# StmPulse-V1-G498043.net
KiCad netlist of a schematic drawn in EAGLE
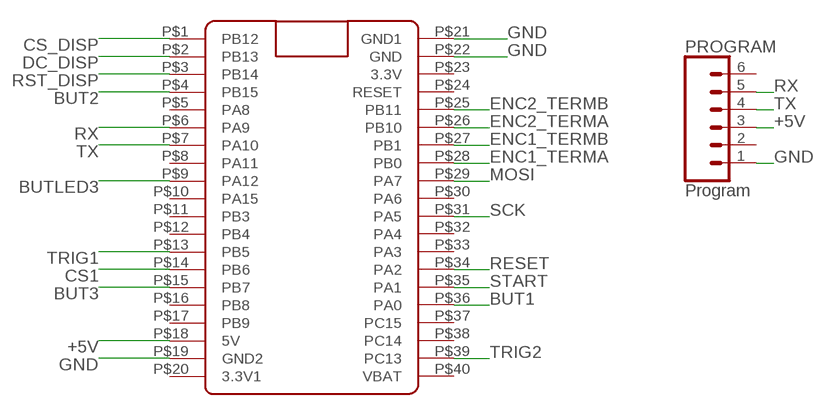
[diagram p0: schematic, sheet 1]
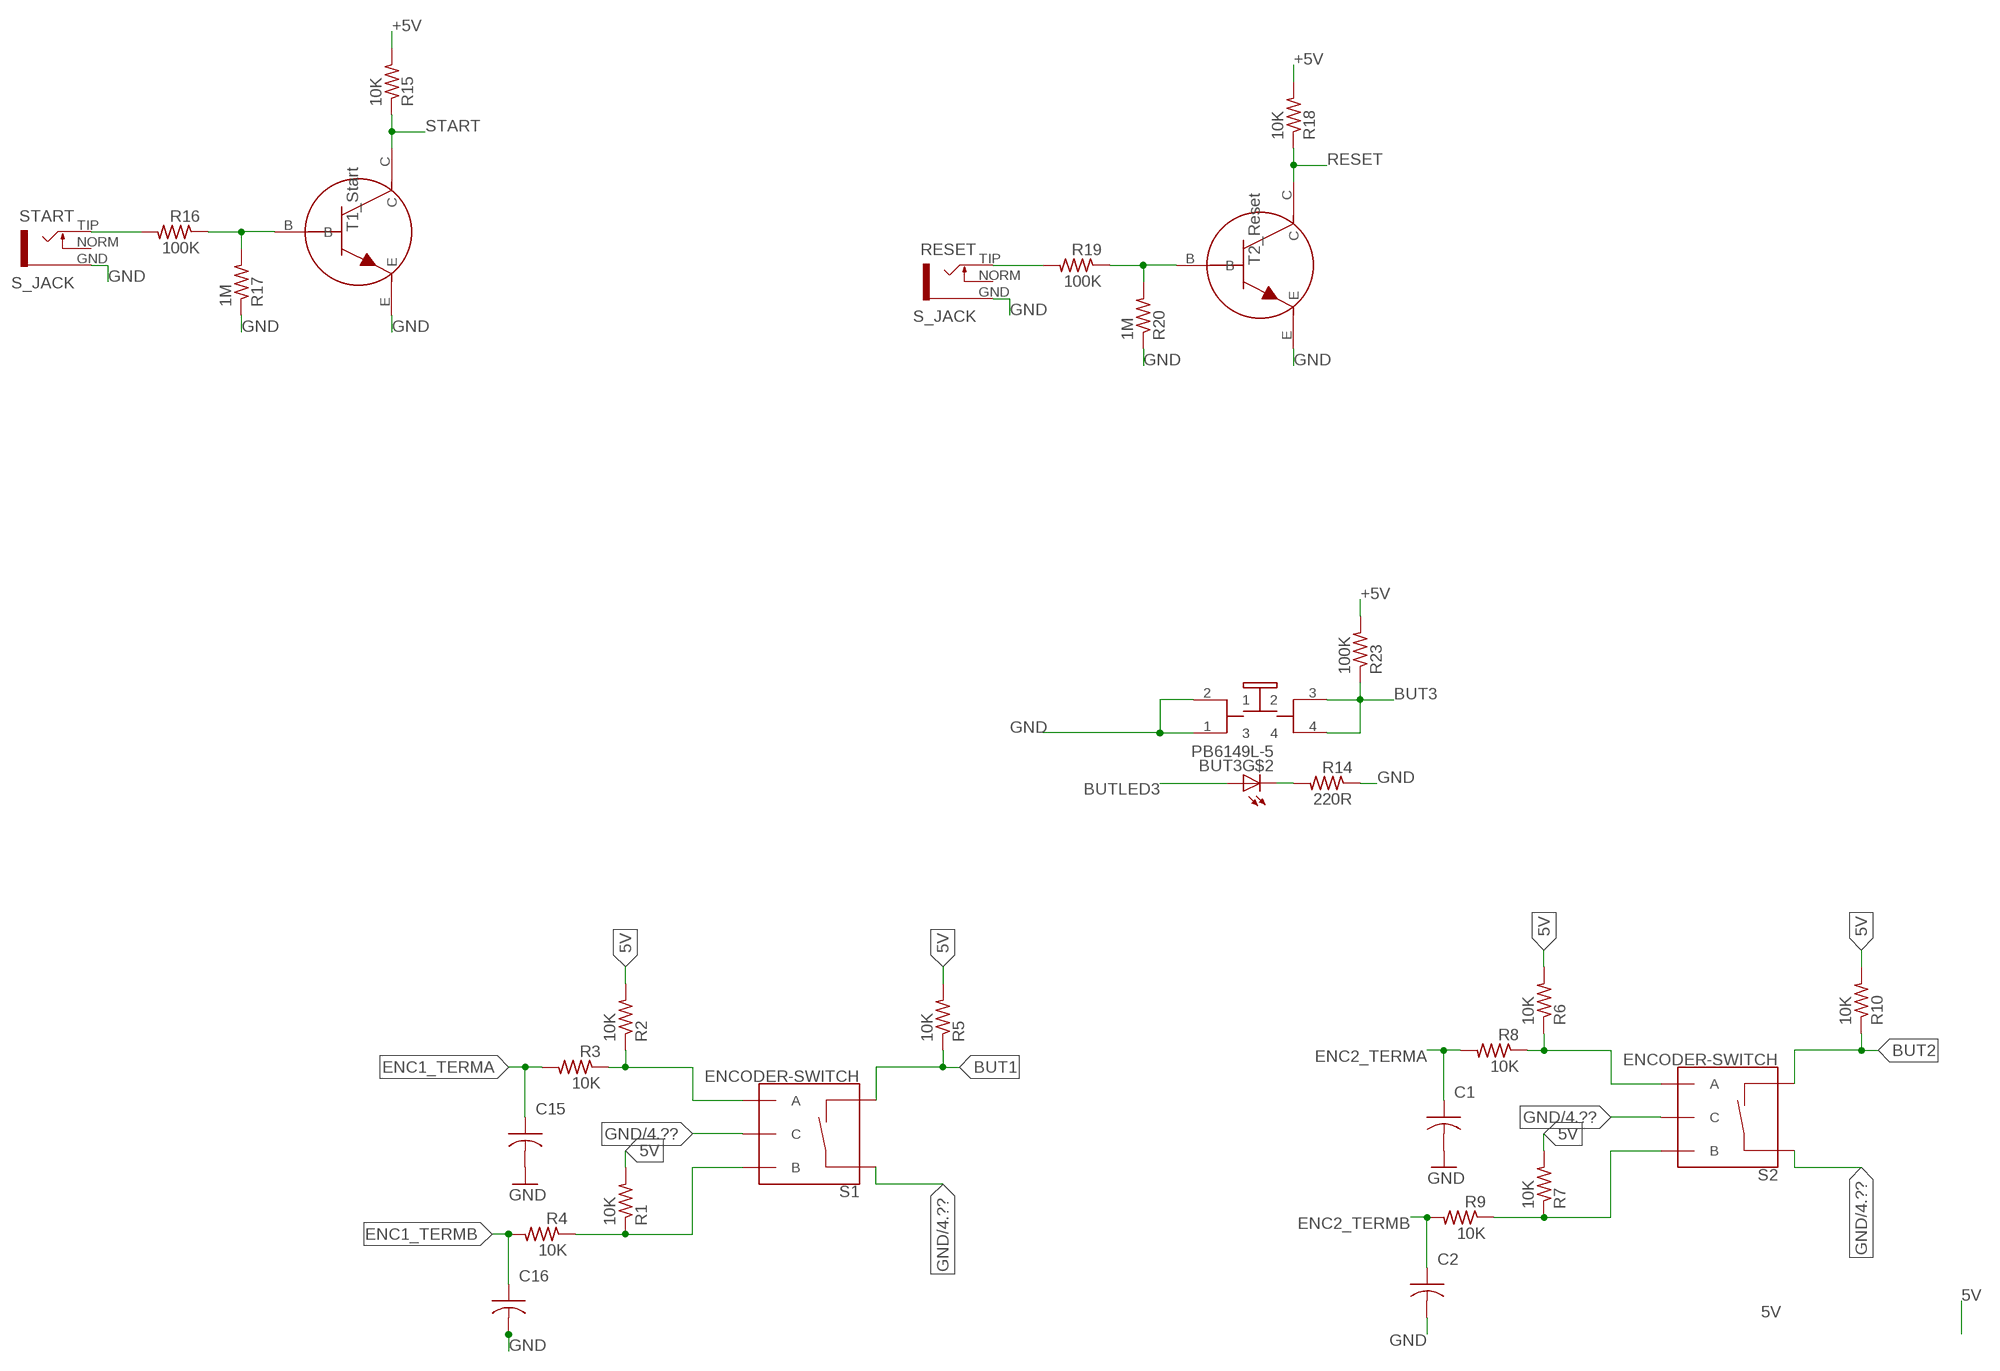
[diagram p1: schematic, sheet 2]
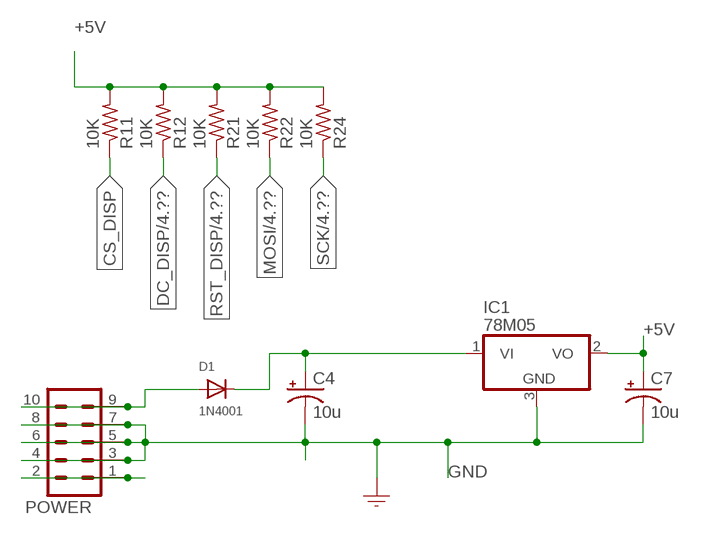
[diagram p2: schematic, sheet 3]
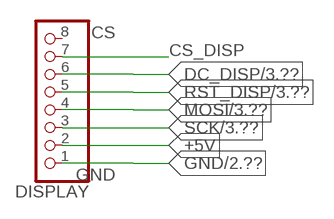
[diagram p3: schematic, sheet 4]
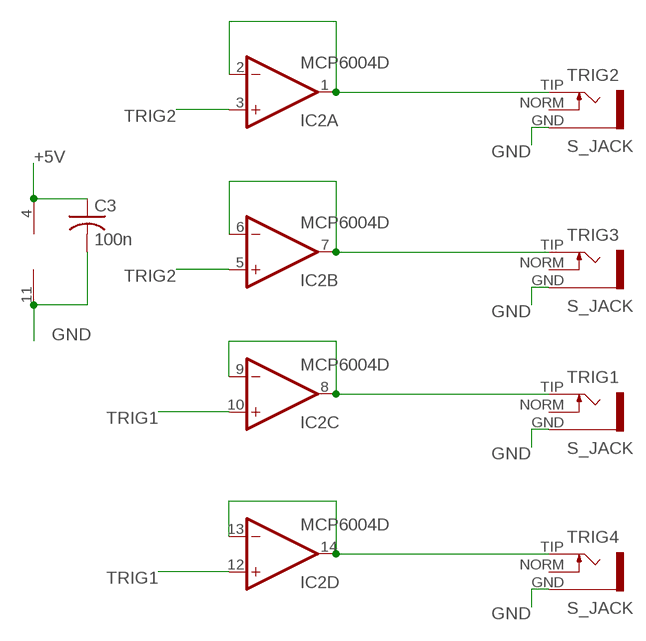
[diagram p4: schematic, sheet 5]
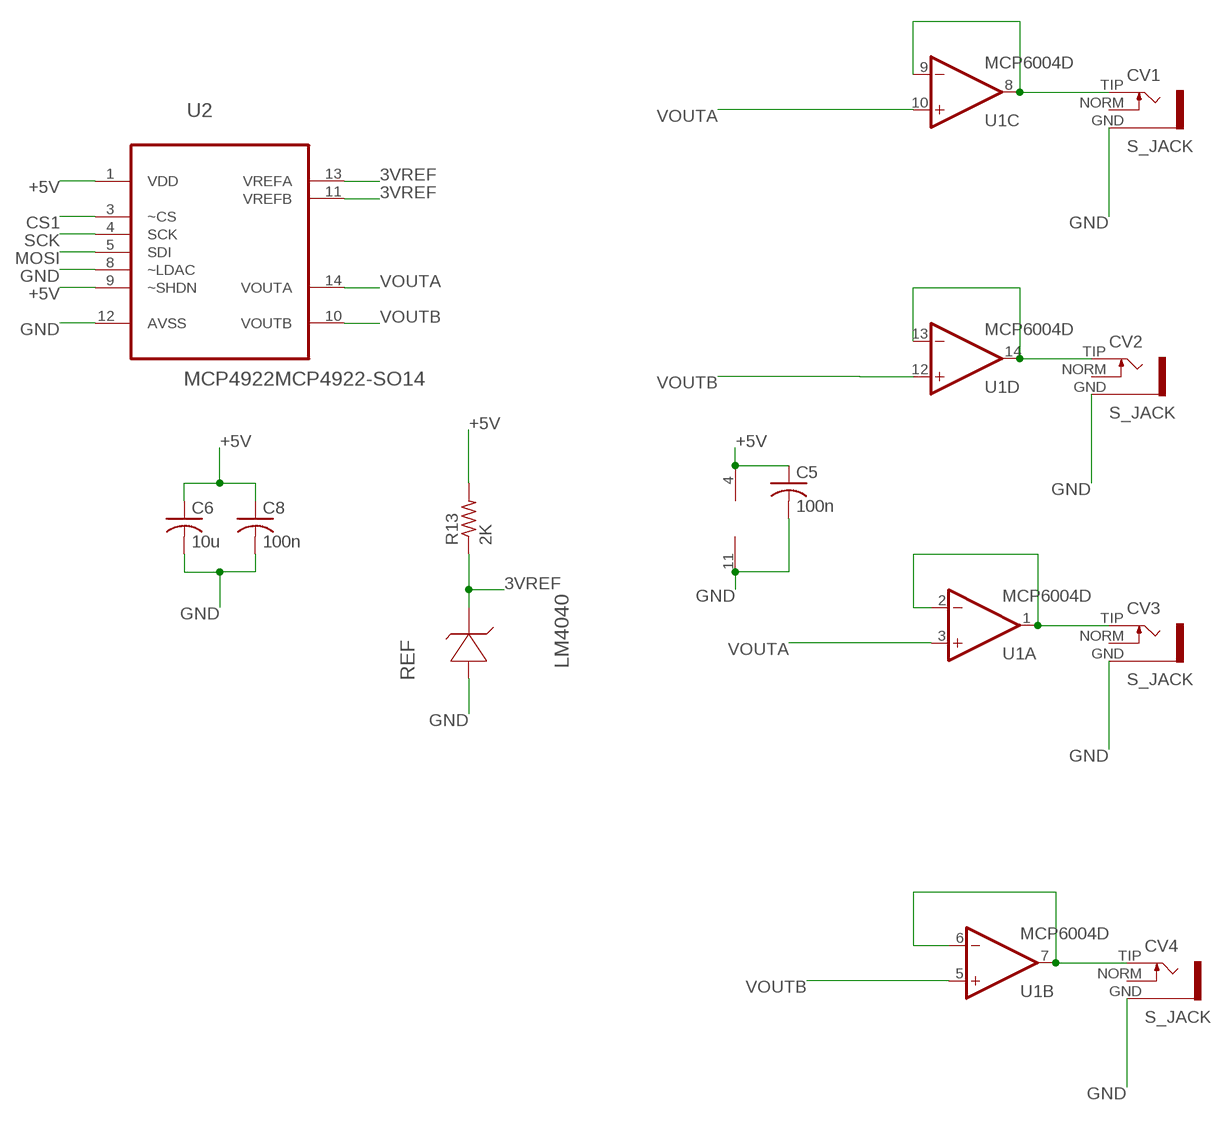
[diagram p5: schematic, sheet 6]

(export (version "E")
  (design (tool "Eeschema 10.0.6"))
  (components
    (comp (ref "C5")
      (value "100n")
      (footprint "eagle-import:C0805K")
      (libsource (lib "eagle-import") (part "C-USC0805K"))
    )
    (comp (ref "C6")
      (value "10u")
      (footprint "eagle-import:C0805K")
      (libsource (lib "eagle-import") (part "C-USC0805K"))
    )
    (comp (ref "C8")
      (value "100n")
      (footprint "eagle-import:C0805K")
      (libsource (lib "eagle-import") (part "C-USC0805K"))
    )
    (comp (ref "CV1")
      (value "S_JACK")
      (footprint "eagle-import:S_JACK")
      (libsource (lib "eagle-import") (part "S_JACK"))
    )
    (comp (ref "CV2")
      (value "S_JACK")
      (footprint "eagle-import:S_JACK")
      (libsource (lib "eagle-import") (part "S_JACK"))
    )
    (comp (ref "CV3")
      (value "S_JACK")
      (footprint "eagle-import:S_JACK")
      (libsource (lib "eagle-import") (part "S_JACK"))
    )
    (comp (ref "CV4")
      (value "S_JACK")
      (footprint "eagle-import:S_JACK")
      (libsource (lib "eagle-import") (part "S_JACK"))
    )
    (comp (ref "R13")
      (value "2K")
      (footprint "eagle-import:R0805")
      (libsource (lib "eagle-import") (part "R-US_R0805"))
    )
    (comp (ref "REF")
      (value "LM4040")
      (footprint "eagle-import:SOT95P237X112-3N")
      (fields
        (field (name "MPN") "LM4040A50IDBZT")
        (field (name "MPN_1") "LM4040A30IDBZT")
        (field (name "RS-PART") "809-6343")
      )
      (libsource (lib "eagle-import") (part "LM4040A30IDBZT"))
    )
    (comp (ref "U1")
      (value "MCP6004D")
      (footprint "eagle-import:SO14")
      (fields (field (name "RS-PART") "628-3481 (10)"))
      (libsource (lib "eagle-import") (part "MCP6004D"))
    )
    (comp (ref "U2")
      (value "MCP4922MCP4922-SO14")
      (footprint "eagle-import:SO14")
      (fields (field (name "RS-PART") "402-910 "))
      (libsource (lib "eagle-import") (part "MCP4922MCP4922-SO14"))
    )
    (comp (ref "C3")
      (value "100n")
      (footprint "eagle-import:C0805K")
      (libsource (lib "eagle-import") (part "C-USC0805K"))
    )
    (comp (ref "IC2")
      (value "MCP6004D")
      (footprint "eagle-import:SO14")
      (libsource (lib "eagle-import") (part "MCP6004D"))
    )
    (comp (ref "TRIG1")
      (value "S_JACK")
      (footprint "eagle-import:S_JACK")
      (libsource (lib "eagle-import") (part "S_JACK"))
    )
    (comp (ref "TRIG2")
      (value "S_JACK")
      (footprint "eagle-import:S_JACK")
      (libsource (lib "eagle-import") (part "S_JACK"))
    )
    (comp (ref "TRIG3")
      (value "S_JACK")
      (footprint "eagle-import:S_JACK")
      (libsource (lib "eagle-import") (part "S_JACK"))
    )
    (comp (ref "TRIG4")
      (value "S_JACK")
      (footprint "eagle-import:S_JACK")
      (libsource (lib "eagle-import") (part "S_JACK"))
    )
    (comp (ref "PROGRAM")
      (value "Program")
      (footprint "eagle-import:1X06")
      (libsource (lib "eagle-import") (part "CONN_06SILK_FEMALE_PTH"))
    )
    (comp (ref "U$1")
      (value "Blue Pill")
      (footprint "eagle-import:BLUE_PILL")
      (libsource (lib "eagle-import") (part "BLUE_PILL"))
    )
    (comp (ref "DISPLAY")
      (value "MICROBUILDER_HEADER-1X8ROUND")
      (footprint "eagle-import:MICROBUILDER_1X08_ROUND")
      (libsource (lib "eagle-import") (part "MICROBUILDER_HEADER-1X8ROUND"))
    )
    (comp (ref "C4")
      (value "10u")
      (footprint "eagle-import:153CLV-0505")
      (libsource (lib "eagle-import") (part "CAPACITOR_POL-US153CLV-0505"))
    )
    (comp (ref "C7")
      (value "10u")
      (footprint "eagle-import:153CLV-0505")
      (libsource (lib "eagle-import") (part "CAPACITOR_POL-US153CLV-0505"))
    )
    (comp (ref "D1")
      (value "1N4001")
      (footprint "eagle-import:SMADIODE")
      (libsource (lib "eagle-import") (part "DIODESMA"))
    )
    (comp (ref "IC1")
      (value "78M05")
      (footprint "eagle-import:TO252")
      (libsource (lib "eagle-import") (part "VOLTAGE_REG_POSDT05"))
    )
    (comp (ref "POWER")
      (value "CONN_05X2SHD_SMD")
      (footprint "eagle-import:2X5-SHROUDED_SMD")
      (fields (field (name "RS-PART") "828-1783"))
      (libsource (lib "eagle-import") (part "CONN_05X2SHD_SMD"))
    )
    (comp (ref "R11")
      (value "10K")
      (footprint "eagle-import:R0805")
      (libsource (lib "eagle-import") (part "R-US_R0805"))
    )
    (comp (ref "R12")
      (value "10K")
      (footprint "eagle-import:R0805")
      (libsource (lib "eagle-import") (part "R-US_R0805"))
    )
    (comp (ref "R21")
      (value "10K")
      (footprint "eagle-import:R0805")
      (libsource (lib "eagle-import") (part "R-US_R0805"))
    )
    (comp (ref "R22")
      (value "10K")
      (footprint "eagle-import:R0805")
      (libsource (lib "eagle-import") (part "R-US_R0805"))
    )
    (comp (ref "R24")
      (value "10K")
      (footprint "eagle-import:R0805")
      (libsource (lib "eagle-import") (part "R-US_R0805"))
    )
    (comp (ref "BUT3")
      (value "PB6149L-5")
      (footprint "eagle-import:PB6149L")
      (libsource (lib "eagle-import") (part "PB6149L-5"))
    )
    (comp (ref "C1")
      (value "10nF")
      (footprint "eagle-import:C0805")
      (libsource (lib "eagle-import") (part "C-USC0805"))
    )
    (comp (ref "C2")
      (value "10nF")
      (footprint "eagle-import:C0805")
      (libsource (lib "eagle-import") (part "C-USC0805"))
    )
    (comp (ref "C15")
      (value "10nF")
      (footprint "eagle-import:C0805")
      (libsource (lib "eagle-import") (part "C-USC0805"))
    )
    (comp (ref "C16")
      (value "10nF")
      (footprint "eagle-import:C0805")
      (libsource (lib "eagle-import") (part "C-USC0805"))
    )
    (comp (ref "R1")
      (value "10K")
      (footprint "eagle-import:R0805")
      (libsource (lib "eagle-import") (part "R-US_R0805"))
    )
    (comp (ref "R2")
      (value "10K")
      (footprint "eagle-import:R0805")
      (libsource (lib "eagle-import") (part "R-US_R0805"))
    )
    (comp (ref "R3")
      (value "10K")
      (footprint "eagle-import:R0805")
      (libsource (lib "eagle-import") (part "R-US_R0805"))
    )
    (comp (ref "R4")
      (value "10K")
      (footprint "eagle-import:R0805")
      (libsource (lib "eagle-import") (part "R-US_R0805"))
    )
    (comp (ref "R5")
      (value "10K")
      (footprint "eagle-import:R0805")
      (libsource (lib "eagle-import") (part "R-US_R0805"))
    )
    (comp (ref "R6")
      (value "10K")
      (footprint "eagle-import:R0805")
      (libsource (lib "eagle-import") (part "R-US_R0805"))
    )
    (comp (ref "R7")
      (value "10K")
      (footprint "eagle-import:R0805")
      (libsource (lib "eagle-import") (part "R-US_R0805"))
    )
    (comp (ref "R8")
      (value "10K")
      (footprint "eagle-import:R0805")
      (libsource (lib "eagle-import") (part "R-US_R0805"))
    )
    (comp (ref "R9")
      (value "10K")
      (footprint "eagle-import:R0805")
      (libsource (lib "eagle-import") (part "R-US_R0805"))
    )
    (comp (ref "R10")
      (value "10K")
      (footprint "eagle-import:R0805")
      (libsource (lib "eagle-import") (part "R-US_R0805"))
    )
    (comp (ref "R14")
      (value "220R")
      (footprint "eagle-import:R0805")
      (libsource (lib "eagle-import") (part "R-US_R0805"))
    )
    (comp (ref "R15")
      (value "10K")
      (footprint "eagle-import:R0805")
      (libsource (lib "eagle-import") (part "R-US_R0805"))
    )
    (comp (ref "R16")
      (value "100K")
      (footprint "eagle-import:R0805")
      (libsource (lib "eagle-import") (part "R-US_R0805"))
    )
    (comp (ref "R17")
      (value "1M")
      (footprint "eagle-import:R0805")
      (libsource (lib "eagle-import") (part "R-US_R0805"))
    )
    (comp (ref "R18")
      (value "10K")
      (footprint "eagle-import:R0805")
      (libsource (lib "eagle-import") (part "R-US_R0805"))
    )
    (comp (ref "R19")
      (value "100K")
      (footprint "eagle-import:R0805")
      (libsource (lib "eagle-import") (part "R-US_R0805"))
    )
    (comp (ref "R20")
      (value "1M")
      (footprint "eagle-import:R0805")
      (libsource (lib "eagle-import") (part "R-US_R0805"))
    )
    (comp (ref "R23")
      (value "100K")
      (footprint "eagle-import:R0805")
      (libsource (lib "eagle-import") (part "R-US_R0805"))
    )
    (comp (ref "RESET")
      (value "S_JACK")
      (footprint "eagle-import:S_JACK")
      (libsource (lib "eagle-import") (part "S_JACK"))
    )
    (comp (ref "S1")
      (value "ENCODER-SWITCH")
      (footprint "eagle-import:ROTARY_ENC_PLAIN")
      (libsource (lib "eagle-import") (part "ENCODER-SWITCH"))
    )
    (comp (ref "S2")
      (value "ENCODER-SWITCH")
      (footprint "eagle-import:ROTARY_ENC_PLAIN")
      (libsource (lib "eagle-import") (part "ENCODER-SWITCH"))
    )
    (comp (ref "START")
      (value "S_JACK")
      (footprint "eagle-import:S_JACK")
      (libsource (lib "eagle-import") (part "S_JACK"))
    )
    (comp (ref "T1_CLOCK")
      (value "2N3904")
      (footprint "eagle-import:TRANSISTOR_SINGLE_N-TYPE")
      (fields (field (name "LABLEL") "T1_Start") (field (name "RS-PART") "725-8616 "))
      (libsource (lib "eagle-import") (part "TRANSISTOR_MMBT3904"))
    )
    (comp (ref "T2_RESET")
      (value "TRANSISTOR_MMBT3904")
      (footprint "eagle-import:TRANSISTOR_SINGLE_N-TYPE")
      (fields (field (name "LABEL") "T2_Reset") (field (name "RS-PART") "725-8616 "))
      (libsource (lib "eagle-import") (part "TRANSISTOR_MMBT3904"))
    )
  )
  (nets
    (net (code "1") (name "+5V") (class "Default")
      (node (ref "C3") (pin "1") (pinfunction "1_1") (pintype "passive"))
      (node (ref "C5") (pin "1") (pinfunction "1_1") (pintype "passive"))
      (node (ref "C6") (pin "1") (pinfunction "1_1") (pintype "passive"))
      (node (ref "C7") (pin "+") (pinfunction "+_+") (pintype "passive"))
      (node (ref "C8") (pin "1") (pinfunction "1_1") (pintype "passive"))
      (node (ref "DISPLAY") (pin "2") (pinfunction "2_2") (pintype "passive"))
      (node (ref "IC1") (pin "2") (pinfunction "VO_2") (pintype "passive"))
      (node (ref "IC2") (pin "4") (pinfunction "V+_4") (pintype "power_in"))
      (node (ref "PROGRAM") (pin "3") (pinfunction "3_3") (pintype "passive"))
      (node (ref "R11") (pin "2") (pinfunction "2_2") (pintype "passive"))
      (node (ref "R12") (pin "2") (pinfunction "2_2") (pintype "passive"))
      (node (ref "R13") (pin "2") (pinfunction "2_2") (pintype "passive"))
      (node (ref "R15") (pin "2") (pinfunction "2_2") (pintype "passive"))
      (node (ref "R18") (pin "2") (pinfunction "2_2") (pintype "passive"))
      (node (ref "R21") (pin "2") (pinfunction "2_2") (pintype "passive"))
      (node (ref "R22") (pin "2") (pinfunction "2_2") (pintype "passive"))
      (node (ref "R23") (pin "2") (pinfunction "2_2") (pintype "passive"))
      (node (ref "R24") (pin "2") (pinfunction "2_2") (pintype "passive"))
      (node (ref "U$1") (pin "P$18") (pinfunction "5V_P$18") (pintype "bidirectional"))
      (node (ref "U1") (pin "4") (pinfunction "V+_4") (pintype "power_in"))
      (node (ref "U2") (pin "1") (pinfunction "VDD_1") (pintype "power_in"))
      (node (ref "U2") (pin "9") (pinfunction "~{SHDN}_9") (pintype "bidirectional"))
    )
    (net (code "2") (name "3VREF") (class "Default")
      (node (ref "R13") (pin "1") (pinfunction "1_1") (pintype "passive"))
      (node (ref "REF") (pin "1") (pinfunction "CATHODE_1") (pintype "output"))
      (node (ref "U2") (pin "11") (pinfunction "VREFB_11") (pintype "bidirectional"))
      (node (ref "U2") (pin "13") (pinfunction "VREFA_13") (pintype "input"))
    )
    (net (code "3") (name "5V") (class "Default")
      (node (ref "R1") (pin "2") (pinfunction "2_2") (pintype "passive"))
      (node (ref "R10") (pin "2") (pinfunction "2_2") (pintype "passive"))
      (node (ref "R2") (pin "2") (pinfunction "2_2") (pintype "passive"))
      (node (ref "R5") (pin "2") (pinfunction "2_2") (pintype "passive"))
      (node (ref "R6") (pin "2") (pinfunction "2_2") (pintype "passive"))
      (node (ref "R7") (pin "2") (pinfunction "2_2") (pintype "passive"))
    )
    (net (code "4") (name "BUT1") (class "Default")
      (node (ref "R5") (pin "1") (pinfunction "1_1") (pintype "passive"))
      (node (ref "S1") (pin "SW-") (pinfunction "SW-_SW-") (pintype "bidirectional"))
      (node (ref "U$1") (pin "P$36") (pinfunction "PA0_P$36") (pintype "bidirectional"))
    )
    (net (code "5") (name "BUT2") (class "Default")
      (node (ref "R10") (pin "1") (pinfunction "1_1") (pintype "passive"))
      (node (ref "S2") (pin "SW-") (pinfunction "SW-_SW-") (pintype "bidirectional"))
      (node (ref "U$1") (pin "P$4") (pinfunction "PB15_P$4") (pintype "bidirectional"))
    )
    (net (code "6") (name "BUT3") (class "Default")
      (node (ref "BUT3") (pin "3") (pinfunction "2_3") (pintype "bidirectional"))
      (node (ref "BUT3") (pin "4") (pinfunction "4_4") (pintype "bidirectional"))
      (node (ref "R23") (pin "1") (pinfunction "1_1") (pintype "passive"))
      (node (ref "U$1") (pin "P$15") (pinfunction "PB7_P$15") (pintype "bidirectional"))
    )
    (net (code "7") (name "BUTLED3") (class "Default")
      (node (ref "BUT3") (pin "A") (pinfunction "A_A") (pintype "passive"))
      (node (ref "U$1") (pin "P$9") (pinfunction "PA12_P$9") (pintype "bidirectional"))
    )
    (net (code "8") (name "CS1") (class "Default")
      (node (ref "U$1") (pin "P$14") (pinfunction "PB6_P$14") (pintype "bidirectional"))
      (node (ref "U2") (pin "3") (pinfunction "~{CS}_3") (pintype "input"))
    )
    (net (code "9") (name "CS_DISP") (class "Default")
      (node (ref "DISPLAY") (pin "7") (pinfunction "7_7") (pintype "passive"))
      (node (ref "R11") (pin "1") (pinfunction "1_1") (pintype "passive"))
      (node (ref "U$1") (pin "P$1") (pinfunction "PB12_P$1") (pintype "bidirectional"))
    )
    (net (code "10") (name "DC_DISP") (class "Default")
      (node (ref "DISPLAY") (pin "6") (pinfunction "6_6") (pintype "passive"))
      (node (ref "R12") (pin "1") (pinfunction "1_1") (pintype "passive"))
      (node (ref "U$1") (pin "P$2") (pinfunction "PB13_P$2") (pintype "bidirectional"))
    )
    (net (code "11") (name "ENC1_TERMA") (class "Default")
      (node (ref "C15") (pin "1") (pinfunction "1_1") (pintype "passive"))
      (node (ref "R3") (pin "2") (pinfunction "2_2") (pintype "passive"))
      (node (ref "U$1") (pin "P$28") (pinfunction "PB0_P$28") (pintype "bidirectional"))
    )
    (net (code "12") (name "ENC1_TERMB") (class "Default")
      (node (ref "C16") (pin "1") (pinfunction "1_1") (pintype "passive"))
      (node (ref "R4") (pin "2") (pinfunction "2_2") (pintype "passive"))
      (node (ref "U$1") (pin "P$27") (pinfunction "PB1_P$27") (pintype "bidirectional"))
    )
    (net (code "13") (name "ENC2_TERMA") (class "Default")
      (node (ref "C1") (pin "1") (pinfunction "1_1") (pintype "passive"))
      (node (ref "R8") (pin "2") (pinfunction "2_2") (pintype "passive"))
      (node (ref "U$1") (pin "P$26") (pinfunction "PB10_P$26") (pintype "bidirectional"))
    )
    (net (code "14") (name "ENC2_TERMB") (class "Default")
      (node (ref "C2") (pin "1") (pinfunction "1_1") (pintype "passive"))
      (node (ref "R9") (pin "2") (pinfunction "2_2") (pintype "passive"))
      (node (ref "U$1") (pin "P$25") (pinfunction "PB11_P$25") (pintype "bidirectional"))
    )
    (net (code "15") (name "GND") (class "Default")
      (node (ref "BUT3") (pin "1") (pinfunction "3_1") (pintype "bidirectional"))
      (node (ref "BUT3") (pin "2") (pinfunction "1_2") (pintype "bidirectional"))
      (node (ref "C1") (pin "2") (pinfunction "2_2") (pintype "passive"))
      (node (ref "C15") (pin "2") (pinfunction "2_2") (pintype "passive"))
      (node (ref "C16") (pin "2") (pinfunction "2_2") (pintype "passive"))
      (node (ref "C2") (pin "2") (pinfunction "2_2") (pintype "passive"))
      (node (ref "C3") (pin "2") (pinfunction "2_2") (pintype "passive"))
      (node (ref "C4") (pin "-") (pinfunction "-_-") (pintype "passive"))
      (node (ref "C5") (pin "2") (pinfunction "2_2") (pintype "passive"))
      (node (ref "C6") (pin "2") (pinfunction "2_2") (pintype "passive"))
      (node (ref "C7") (pin "-") (pinfunction "-_-") (pintype "passive"))
      (node (ref "C8") (pin "2") (pinfunction "2_2") (pintype "passive"))
      (node (ref "CV1") (pin "GND") (pinfunction "GND_GND") (pintype "passive"))
      (node (ref "CV2") (pin "GND") (pinfunction "GND_GND") (pintype "passive"))
      (node (ref "CV3") (pin "GND") (pinfunction "GND_GND") (pintype "passive"))
      (node (ref "CV4") (pin "GND") (pinfunction "GND_GND") (pintype "passive"))
      (node (ref "DISPLAY") (pin "1") (pinfunction "1_1") (pintype "passive"))
      (node (ref "IC1") (pin "3") (pinfunction "GND_3") (pintype "passive"))
      (node (ref "IC2") (pin "11") (pinfunction "V-_11") (pintype "power_in"))
      (node (ref "POWER") (pin "3") (pinfunction "3_3") (pintype "passive"))
      (node (ref "POWER") (pin "4") (pinfunction "4_4") (pintype "passive"))
      (node (ref "POWER") (pin "5") (pinfunction "5_5") (pintype "passive"))
      (node (ref "POWER") (pin "6") (pinfunction "6_6") (pintype "passive"))
      (node (ref "POWER") (pin "7") (pinfunction "7_7") (pintype "passive"))
      (node (ref "POWER") (pin "8") (pinfunction "8_8") (pintype "passive"))
      (node (ref "PROGRAM") (pin "1") (pinfunction "1_1") (pintype "passive"))
      (node (ref "R14") (pin "1") (pinfunction "1_1") (pintype "passive"))
      (node (ref "R17") (pin "1") (pinfunction "1_1") (pintype "passive"))
      (node (ref "R20") (pin "1") (pinfunction "1_1") (pintype "passive"))
      (node (ref "REF") (pin "2") (pinfunction "ANODE_2") (pintype "input"))
      (node (ref "RESET") (pin "GND") (pinfunction "GND_GND") (pintype "passive"))
      (node (ref "S1") (pin "C") (pinfunction "C_C") (pintype "bidirectional"))
      (node (ref "S1") (pin "SW+") (pinfunction "SW+_SW+") (pintype "bidirectional"))
      (node (ref "S2") (pin "C") (pinfunction "C_C") (pintype "bidirectional"))
      (node (ref "S2") (pin "SW+") (pinfunction "SW+_SW+") (pintype "bidirectional"))
      (node (ref "START") (pin "GND") (pinfunction "GND_GND") (pintype "passive"))
      (node (ref "T1_CLOCK") (pin "E") (pinfunction "E_E") (pintype "bidirectional"))
      (node (ref "T2_RESET") (pin "E") (pinfunction "E_E") (pintype "bidirectional"))
      (node (ref "TRIG1") (pin "GND") (pinfunction "GND_GND") (pintype "passive"))
      (node (ref "TRIG2") (pin "GND") (pinfunction "GND_GND") (pintype "passive"))
      (node (ref "TRIG3") (pin "GND") (pinfunction "GND_GND") (pintype "passive"))
      (node (ref "TRIG4") (pin "GND") (pinfunction "GND_GND") (pintype "passive"))
      (node (ref "U$1") (pin "P$19") (pinfunction "GND2_P$19") (pintype "bidirectional"))
      (node (ref "U$1") (pin "P$21") (pinfunction "GND1_P$21") (pintype "power_in"))
      (node (ref "U$1") (pin "P$22") (pinfunction "GND_P$22") (pintype "bidirectional"))
      (node (ref "U1") (pin "11") (pinfunction "V-_11") (pintype "power_in"))
      (node (ref "U2") (pin "12") (pinfunction "AVSS_12") (pintype "passive"))
      (node (ref "U2") (pin "8") (pinfunction "~{LDAC}_8") (pintype "input"))
    )
    (net (code "16") (name "MOSI") (class "Default")
      (node (ref "DISPLAY") (pin "4") (pinfunction "4_4") (pintype "passive"))
      (node (ref "R22") (pin "1") (pinfunction "1_1") (pintype "passive"))
      (node (ref "U$1") (pin "P$29") (pinfunction "PA7_P$29") (pintype "bidirectional"))
      (node (ref "U2") (pin "5") (pinfunction "SDI_5") (pintype "input"))
    )
    (net (code "17") (name "Net-(BUT3B-C)") (class "Default")
      (node (ref "BUT3") (pin "K") (pinfunction "C_K") (pintype "passive"))
      (node (ref "R14") (pin "2") (pinfunction "2_2") (pintype "passive"))
    )
    (net (code "18") (name "Net-(D1-PadA)") (class "Default")
      (node (ref "D1") (pin "A") (pinfunction "A_A") (pintype "passive"))
      (node (ref "POWER") (pin "10") (pinfunction "10_10") (pintype "passive"))
      (node (ref "POWER") (pin "9") (pinfunction "9_9") (pintype "passive"))
    )
    (net (code "19") (name "Net-(IC1-VI)") (class "Default")
      (node (ref "C4") (pin "+") (pinfunction "+_+") (pintype "passive"))
      (node (ref "D1") (pin "C") (pinfunction "C_C") (pintype "passive"))
      (node (ref "IC1") (pin "1") (pinfunction "VI_1") (pintype "input"))
    )
    (net (code "20") (name "Net-(IC2A--IN)") (class "Default")
      (node (ref "IC2") (pin "1") (pinfunction "OUT_1") (pintype "output"))
      (node (ref "IC2") (pin "2") (pinfunction "-IN_2") (pintype "input"))
      (node (ref "TRIG2") (pin "TIP") (pinfunction "TIP_TIP") (pintype "passive"))
    )
    (net (code "21") (name "Net-(IC2B--IN)") (class "Default")
      (node (ref "IC2") (pin "6") (pinfunction "-IN_6") (pintype "input"))
      (node (ref "IC2") (pin "7") (pinfunction "OUT_7") (pintype "output"))
      (node (ref "TRIG3") (pin "TIP") (pinfunction "TIP_TIP") (pintype "passive"))
    )
    (net (code "22") (name "Net-(IC2C--IN)") (class "Default")
      (node (ref "IC2") (pin "8") (pinfunction "OUT_8") (pintype "output"))
      (node (ref "IC2") (pin "9") (pinfunction "-IN_9") (pintype "input"))
      (node (ref "TRIG1") (pin "TIP") (pinfunction "TIP_TIP") (pintype "passive"))
    )
    (net (code "23") (name "Net-(IC2D--IN)") (class "Default")
      (node (ref "IC2") (pin "13") (pinfunction "-IN_13") (pintype "input"))
      (node (ref "IC2") (pin "14") (pinfunction "OUT_14") (pintype "output"))
      (node (ref "TRIG4") (pin "TIP") (pinfunction "TIP_TIP") (pintype "passive"))
    )
    (net (code "24") (name "Net-(POWER-Pad1)") (class "Default")
      (node (ref "POWER") (pin "1") (pinfunction "1_1") (pintype "passive"))
      (node (ref "POWER") (pin "2") (pinfunction "2_2") (pintype "passive"))
    )
    (net (code "25") (name "Net-(R1-Pad1)") (class "Default")
      (node (ref "R1") (pin "1") (pinfunction "1_1") (pintype "passive"))
      (node (ref "R4") (pin "1") (pinfunction "1_1") (pintype "passive"))
      (node (ref "S1") (pin "B") (pinfunction "B_B") (pintype "bidirectional"))
    )
    (net (code "26") (name "Net-(R2-Pad1)") (class "Default")
      (node (ref "R2") (pin "1") (pinfunction "1_1") (pintype "passive"))
      (node (ref "R3") (pin "1") (pinfunction "1_1") (pintype "passive"))
      (node (ref "S1") (pin "A") (pinfunction "A_A") (pintype "bidirectional"))
    )
    (net (code "27") (name "Net-(R6-Pad1)") (class "Default")
      (node (ref "R6") (pin "1") (pinfunction "1_1") (pintype "passive"))
      (node (ref "R8") (pin "1") (pinfunction "1_1") (pintype "passive"))
      (node (ref "S2") (pin "A") (pinfunction "A_A") (pintype "bidirectional"))
    )
    (net (code "28") (name "Net-(R7-Pad1)") (class "Default")
      (node (ref "R7") (pin "1") (pinfunction "1_1") (pintype "passive"))
      (node (ref "R9") (pin "1") (pinfunction "1_1") (pintype "passive"))
      (node (ref "S2") (pin "B") (pinfunction "B_B") (pintype "bidirectional"))
    )
    (net (code "29") (name "Net-(R16-Pad1)") (class "Default")
      (node (ref "R16") (pin "1") (pinfunction "1_1") (pintype "passive"))
      (node (ref "R17") (pin "2") (pinfunction "2_2") (pintype "passive"))
      (node (ref "T1_CLOCK") (pin "B") (pinfunction "B_B") (pintype "bidirectional"))
    )
    (net (code "30") (name "Net-(R16-Pad2)") (class "Default")
      (node (ref "R16") (pin "2") (pinfunction "2_2") (pintype "passive"))
      (node (ref "START") (pin "TIP") (pinfunction "TIP_TIP") (pintype "passive"))
    )
    (net (code "31") (name "Net-(R19-Pad1)") (class "Default")
      (node (ref "R19") (pin "1") (pinfunction "1_1") (pintype "passive"))
      (node (ref "R20") (pin "2") (pinfunction "2_2") (pintype "passive"))
      (node (ref "T2_RESET") (pin "B") (pinfunction "B_B") (pintype "bidirectional"))
    )
    (net (code "32") (name "Net-(R19-Pad2)") (class "Default")
      (node (ref "R19") (pin "2") (pinfunction "2_2") (pintype "passive"))
      (node (ref "RESET") (pin "TIP") (pinfunction "TIP_TIP") (pintype "passive"))
    )
    (net (code "33") (name "Net-(U1A--IN)") (class "Default")
      (node (ref "CV3") (pin "TIP") (pinfunction "TIP_TIP") (pintype "passive"))
      (node (ref "U1") (pin "1") (pinfunction "OUT_1") (pintype "output"))
      (node (ref "U1") (pin "2") (pinfunction "-IN_2") (pintype "input"))
    )
    (net (code "34") (name "Net-(U1B--IN)") (class "Default")
      (node (ref "CV4") (pin "TIP") (pinfunction "TIP_TIP") (pintype "passive"))
      (node (ref "U1") (pin "6") (pinfunction "-IN_6") (pintype "input"))
      (node (ref "U1") (pin "7") (pinfunction "OUT_7") (pintype "output"))
    )
    (net (code "35") (name "Net-(U1C--IN)") (class "Default")
      (node (ref "CV1") (pin "TIP") (pinfunction "TIP_TIP") (pintype "passive"))
      (node (ref "U1") (pin "8") (pinfunction "OUT_8") (pintype "output"))
      (node (ref "U1") (pin "9") (pinfunction "-IN_9") (pintype "input"))
    )
    (net (code "36") (name "Net-(U1D--IN)") (class "Default")
      (node (ref "CV2") (pin "TIP") (pinfunction "TIP_TIP") (pintype "passive"))
      (node (ref "U1") (pin "13") (pinfunction "-IN_13") (pintype "input"))
      (node (ref "U1") (pin "14") (pinfunction "OUT_14") (pintype "output"))
    )
    (net (code "37") (name "RESET") (class "Default")
      (node (ref "R18") (pin "1") (pinfunction "1_1") (pintype "passive"))
      (node (ref "T2_RESET") (pin "C") (pinfunction "C_C") (pintype "bidirectional"))
      (node (ref "U$1") (pin "P$34") (pinfunction "PA2_P$34") (pintype "bidirectional"))
    )
    (net (code "38") (name "RST_DISP") (class "Default")
      (node (ref "DISPLAY") (pin "5") (pinfunction "5_5") (pintype "passive"))
      (node (ref "R21") (pin "1") (pinfunction "1_1") (pintype "passive"))
      (node (ref "U$1") (pin "P$3") (pinfunction "PB14_P$3") (pintype "bidirectional"))
    )
    (net (code "39") (name "RX") (class "Default")
      (node (ref "PROGRAM") (pin "5") (pinfunction "5_5") (pintype "passive"))
      (node (ref "U$1") (pin "P$6") (pinfunction "PA9_P$6") (pintype "bidirectional"))
    )
    (net (code "40") (name "SCK") (class "Default")
      (node (ref "DISPLAY") (pin "3") (pinfunction "3_3") (pintype "passive"))
      (node (ref "R24") (pin "1") (pinfunction "1_1") (pintype "passive"))
      (node (ref "U$1") (pin "P$31") (pinfunction "PA5_P$31") (pintype "bidirectional"))
      (node (ref "U2") (pin "4") (pinfunction "SCK_4") (pintype "input"))
    )
    (net (code "41") (name "START") (class "Default")
      (node (ref "R15") (pin "1") (pinfunction "1_1") (pintype "passive"))
      (node (ref "T1_CLOCK") (pin "C") (pinfunction "C_C") (pintype "bidirectional"))
      (node (ref "U$1") (pin "P$35") (pinfunction "PA1_P$35") (pintype "bidirectional"))
    )
    (net (code "42") (name "TRIG1") (class "Default")
      (node (ref "IC2") (pin "10") (pinfunction "+IN_10") (pintype "input"))
      (node (ref "IC2") (pin "12") (pinfunction "+IN_12") (pintype "input"))
      (node (ref "U$1") (pin "P$13") (pinfunction "PB5_P$13") (pintype "bidirectional"))
    )
    (net (code "43") (name "TRIG2") (class "Default")
      (node (ref "IC2") (pin "3") (pinfunction "+IN_3") (pintype "input"))
      (node (ref "IC2") (pin "5") (pinfunction "+IN_5") (pintype "input"))
      (node (ref "U$1") (pin "P$39") (pinfunction "PC13_P$39") (pintype "bidirectional"))
    )
    (net (code "44") (name "TX") (class "Default")
      (node (ref "PROGRAM") (pin "4") (pinfunction "4_4") (pintype "passive"))
      (node (ref "U$1") (pin "P$7") (pinfunction "PA10_P$7") (pintype "bidirectional"))
    )
    (net (code "45") (name "VOUTA") (class "Default")
      (node (ref "U1") (pin "10") (pinfunction "+IN_10") (pintype "input"))
      (node (ref "U1") (pin "3") (pinfunction "+IN_3") (pintype "input"))
      (node (ref "U2") (pin "14") (pinfunction "VOUTA_14") (pintype "output"))
    )
    (net (code "46") (name "VOUTB") (class "Default")
      (node (ref "U1") (pin "12") (pinfunction "+IN_12") (pintype "input"))
      (node (ref "U1") (pin "5") (pinfunction "+IN_5") (pintype "input"))
      (node (ref "U2") (pin "10") (pinfunction "VOUTB_10") (pintype "output"))
    )
    (net (code "47") (name "unconnected-(CV1-PadNORM)") (class "Default")
      (node (ref "CV1") (pin "NORM") (pinfunction "NORM_NORM") (pintype "passive"))
    )
    (net (code "48") (name "unconnected-(CV2-PadNORM)") (class "Default")
      (node (ref "CV2") (pin "NORM") (pinfunction "NORM_NORM") (pintype "passive"))
    )
    (net (code "49") (name "unconnected-(CV3-PadNORM)") (class "Default")
      (node (ref "CV3") (pin "NORM") (pinfunction "NORM_NORM") (pintype "passive"))
    )
    (net (code "50") (name "unconnected-(CV4-PadNORM)") (class "Default")
      (node (ref "CV4") (pin "NORM") (pinfunction "NORM_NORM") (pintype "passive"))
    )
    (net (code "51") (name "unconnected-(DISPLAY-Pad8)") (class "Default")
      (node (ref "DISPLAY") (pin "8") (pinfunction "8_8") (pintype "passive"))
    )
    (net (code "52") (name "unconnected-(PROGRAM-Pad2)") (class "Default")
      (node (ref "PROGRAM") (pin "2") (pinfunction "2_2") (pintype "passive"))
    )
    (net (code "53") (name "unconnected-(PROGRAM-Pad6)") (class "Default")
      (node (ref "PROGRAM") (pin "6") (pinfunction "6_6") (pintype "passive"))
    )
    (net (code "54") (name "unconnected-(REF-NC-Pad3)") (class "Default")
      (node (ref "REF") (pin "3") (pinfunction "NC_3") (pintype "no_connect"))
    )
    (net (code "55") (name "unconnected-(RESET-PadNORM)") (class "Default")
      (node (ref "RESET") (pin "NORM") (pinfunction "NORM_NORM") (pintype "passive"))
    )
    (net (code "56") (name "unconnected-(START-PadNORM)") (class "Default")
      (node (ref "START") (pin "NORM") (pinfunction "NORM_NORM") (pintype "passive"))
    )
    (net (code "57") (name "unconnected-(TRIG1-PadNORM)") (class "Default")
      (node (ref "TRIG1") (pin "NORM") (pinfunction "NORM_NORM") (pintype "passive"))
    )
    (net (code "58") (name "unconnected-(TRIG2-PadNORM)") (class "Default")
      (node (ref "TRIG2") (pin "NORM") (pinfunction "NORM_NORM") (pintype "passive"))
    )
    (net (code "59") (name "unconnected-(TRIG3-PadNORM)") (class "Default")
      (node (ref "TRIG3") (pin "NORM") (pinfunction "NORM_NORM") (pintype "passive"))
    )
    (net (code "60") (name "unconnected-(TRIG4-PadNORM)") (class "Default")
      (node (ref "TRIG4") (pin "NORM") (pinfunction "NORM_NORM") (pintype "passive"))
    )
    (net (code "61") (name "unconnected-(U$1-3.3V-PadP$23)") (class "Default")
      (node (ref "U$1") (pin "P$23") (pinfunction "3.3V_P$23") (pintype "bidirectional"))
    )
    (net (code "62") (name "unconnected-(U$1-3.3V1-PadP$20)") (class "Default")
      (node (ref "U$1") (pin "P$20") (pinfunction "3.3V1_P$20") (pintype "bidirectional"))
    )
    (net (code "63") (name "unconnected-(U$1-PA3-PadP$33)") (class "Default")
      (node (ref "U$1") (pin "P$33") (pinfunction "PA3_P$33") (pintype "bidirectional"))
    )
    (net (code "64") (name "unconnected-(U$1-PA4-PadP$32)") (class "Default")
      (node (ref "U$1") (pin "P$32") (pinfunction "PA4_P$32") (pintype "bidirectional"))
    )
    (net (code "65") (name "unconnected-(U$1-PA6-PadP$30)") (class "Default")
      (node (ref "U$1") (pin "P$30") (pinfunction "PA6_P$30") (pintype "bidirectional"))
    )
    (net (code "66") (name "unconnected-(U$1-PA8-PadP$5)") (class "Default")
      (node (ref "U$1") (pin "P$5") (pinfunction "PA8_P$5") (pintype "bidirectional"))
    )
    (net (code "67") (name "unconnected-(U$1-PA11-PadP$8)") (class "Default")
      (node (ref "U$1") (pin "P$8") (pinfunction "PA11_P$8") (pintype "bidirectional"))
    )
    (net (code "68") (name "unconnected-(U$1-PA15-PadP$10)") (class "Default")
      (node (ref "U$1") (pin "P$10") (pinfunction "PA15_P$10") (pintype "bidirectional"))
    )
    (net (code "69") (name "unconnected-(U$1-PB3-PadP$11)") (class "Default")
      (node (ref "U$1") (pin "P$11") (pinfunction "PB3_P$11") (pintype "bidirectional"))
    )
    (net (code "70") (name "unconnected-(U$1-PB4-PadP$12)") (class "Default")
      (node (ref "U$1") (pin "P$12") (pinfunction "PB4_P$12") (pintype "bidirectional"))
    )
    (net (code "71") (name "unconnected-(U$1-PB8-PadP$16)") (class "Default")
      (node (ref "U$1") (pin "P$16") (pinfunction "PB8_P$16") (pintype "bidirectional"))
    )
    (net (code "72") (name "unconnected-(U$1-PB9-PadP$17)") (class "Default")
      (node (ref "U$1") (pin "P$17") (pinfunction "PB9_P$17") (pintype "bidirectional"))
    )
    (net (code "73") (name "unconnected-(U$1-PC14-PadP$38)") (class "Default")
      (node (ref "U$1") (pin "P$38") (pinfunction "PC14_P$38") (pintype "bidirectional"))
    )
    (net (code "74") (name "unconnected-(U$1-PC15-PadP$37)") (class "Default")
      (node (ref "U$1") (pin "P$37") (pinfunction "PC15_P$37") (pintype "bidirectional"))
    )
    (net (code "75") (name "unconnected-(U$1-RESET-PadP$24)") (class "Default")
      (node (ref "U$1") (pin "P$24") (pinfunction "RESET_P$24") (pintype "bidirectional"))
    )
    (net (code "76") (name "unconnected-(U$1-VBAT-PadP$40)") (class "Default")
      (node (ref "U$1") (pin "P$40") (pinfunction "VBAT_P$40") (pintype "bidirectional"))
    )
  )
)
